# schaltplan.net
KiCad netlist of a schematic drawn in EAGLE
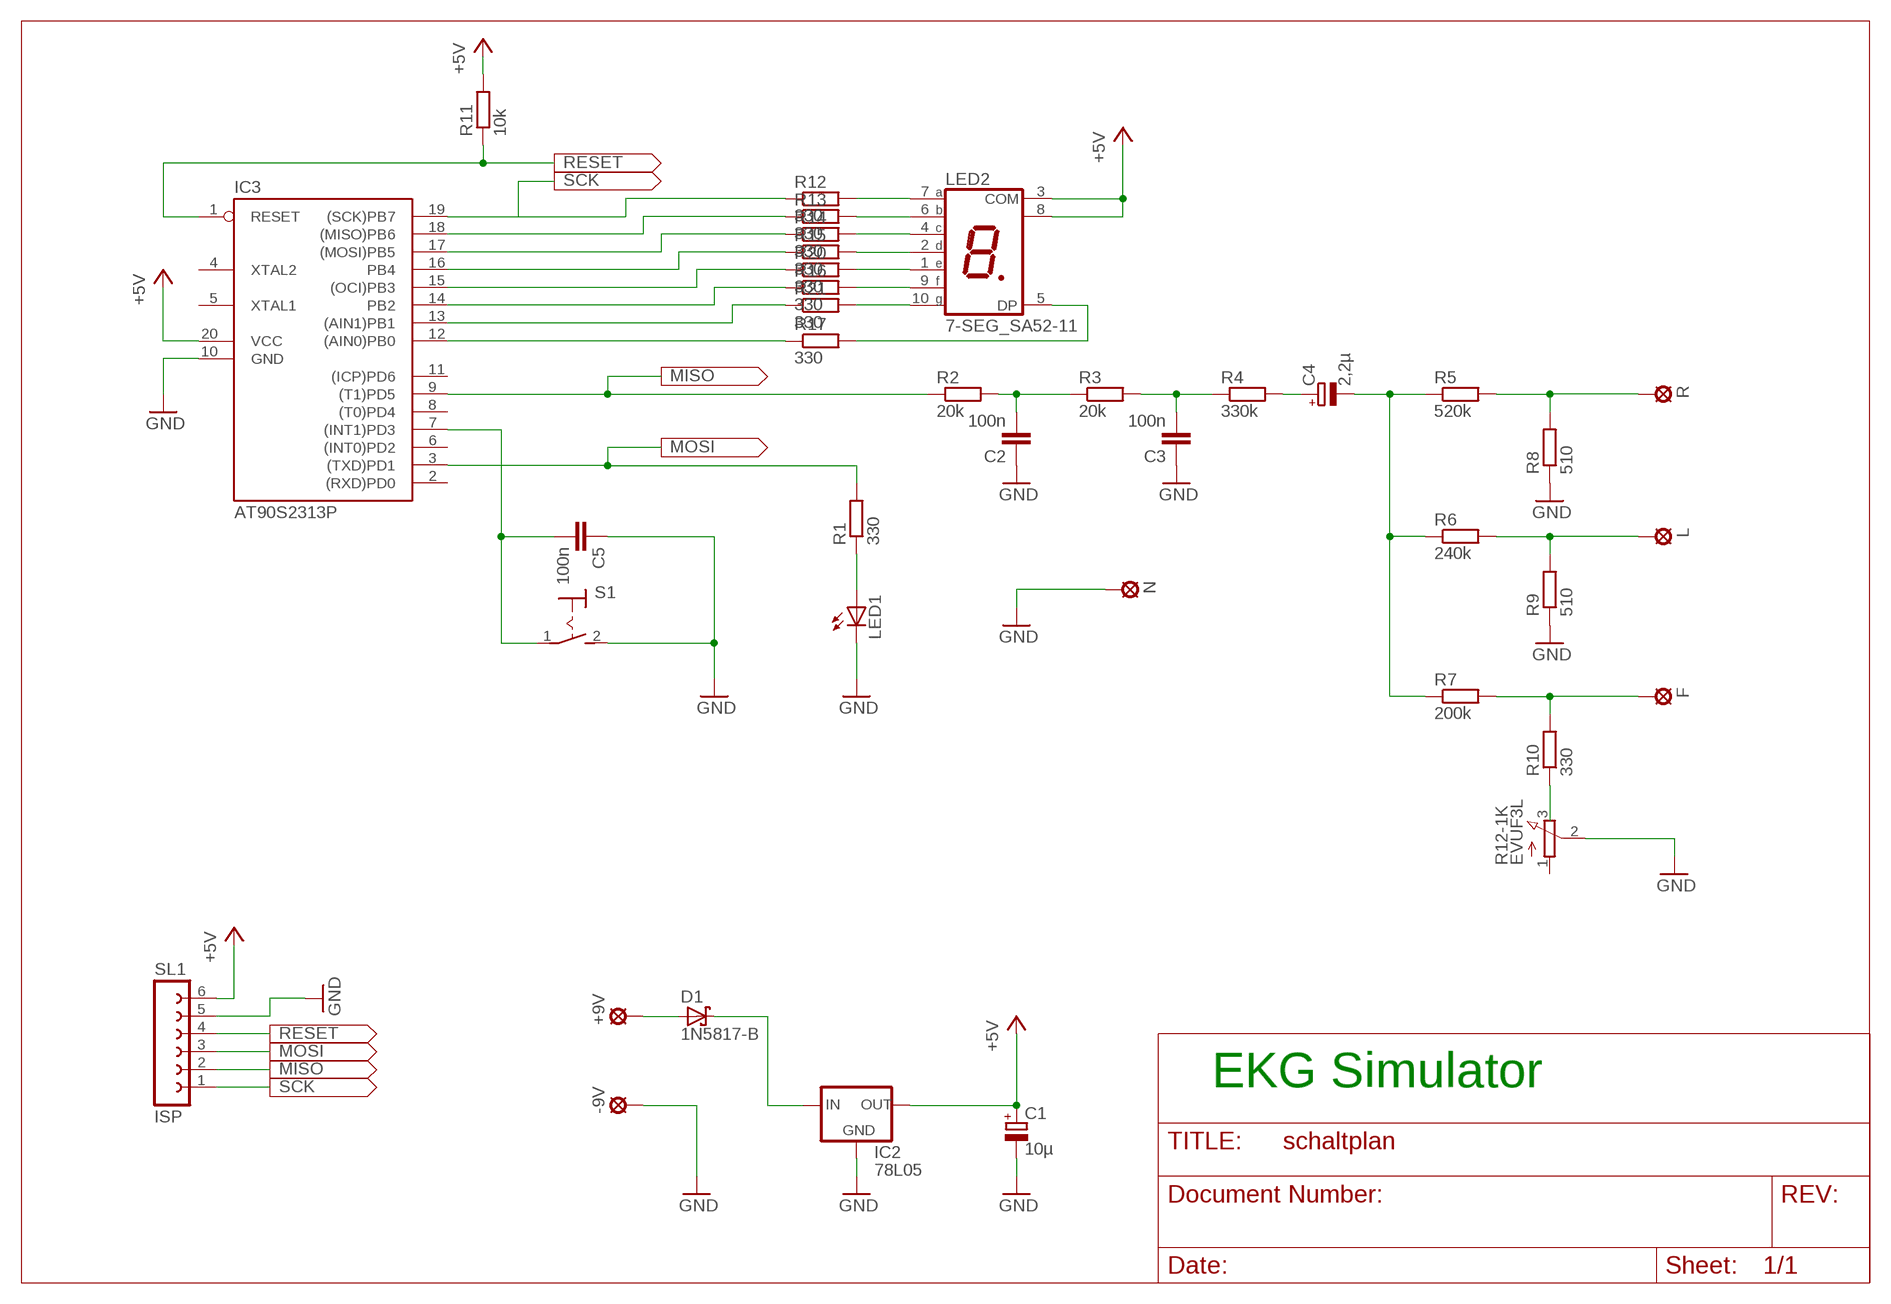
[diagram p0: schematic, sheet 1]

(export (version "E")
  (design (tool "Eeschema 10.0.6"))
  (components
    (comp (ref "+9V")
      (value "LSP10")
      (footprint "eagle-import:LSP10")
      (libsource (lib "eagle-import") (part "LSP10"))
    )
    (comp (ref "-9V")
      (value "LSP10")
      (footprint "eagle-import:LSP10")
      (libsource (lib "eagle-import") (part "LSP10"))
    )
    (comp (ref "C1")
      (value "10µ")
      (footprint "eagle-import:E2,5-6")
      (libsource (lib "eagle-import") (part "CPOL-EUE2.5-6"))
    )
    (comp (ref "C2")
      (value "100n")
      (footprint "eagle-import:C050-025X075")
      (libsource (lib "eagle-import") (part "C-EU050-025X075"))
    )
    (comp (ref "C3")
      (value "100n")
      (footprint "eagle-import:C050-025X075")
      (libsource (lib "eagle-import") (part "C-EU050-025X075"))
    )
    (comp (ref "C4")
      (value "2,2µ")
      (footprint "eagle-import:E2,5-5")
      (libsource (lib "eagle-import") (part "CPOL-EUE2.5-5"))
    )
    (comp (ref "C5")
      (value "100n")
      (footprint "eagle-import:C050-025X075")
      (libsource (lib "eagle-import") (part "C-EU050-025X075"))
    )
    (comp (ref "D1")
      (value "1N5817-B")
      (footprint "eagle-import:DO41-7.6")
      (libsource (lib "eagle-import") (part "1N5817-B"))
    )
    (comp (ref "F")
      (value "LSP10")
      (footprint "eagle-import:LSP10")
      (libsource (lib "eagle-import") (part "LSP10"))
    )
    (comp (ref "IC2")
      (value "78L05")
      (footprint "eagle-import:78LXX")
      (libsource (lib "eagle-import") (part "78LXX"))
    )
    (comp (ref "IC3")
      (value "AT90S2313P")
      (footprint "eagle-import:DIL20")
      (libsource (lib "eagle-import") (part "AT90S2313P"))
    )
    (comp (ref "L")
      (value "LSP10")
      (footprint "eagle-import:LSP10")
      (libsource (lib "eagle-import") (part "LSP10"))
    )
    (comp (ref "LED1")
      (value "LED3MM")
      (footprint "eagle-import:LED3MM")
      (libsource (lib "eagle-import") (part "LED3MM"))
    )
    (comp (ref "LED2")
      (value "7-SEG_SA52-11")
      (footprint "eagle-import:SA52-11")
      (libsource (lib "eagle-import") (part "7-SEG_SA52-11"))
    )
    (comp (ref "N")
      (value "LSP10")
      (footprint "eagle-import:LSP10")
      (libsource (lib "eagle-import") (part "LSP10"))
    )
    (comp (ref "R")
      (value "LSP10")
      (footprint "eagle-import:LSP10")
      (libsource (lib "eagle-import") (part "LSP10"))
    )
    (comp (ref "R1")
      (value "330")
      (footprint "eagle-import:0207_10")
      (libsource (lib "eagle-import") (part "R-EU_0207/10"))
    )
    (comp (ref "R2")
      (value "20k")
      (footprint "eagle-import:0207_10")
      (libsource (lib "eagle-import") (part "R-EU_0207/10"))
    )
    (comp (ref "R3")
      (value "20k")
      (footprint "eagle-import:0207_10")
      (libsource (lib "eagle-import") (part "R-EU_0207/10"))
    )
    (comp (ref "R4")
      (value "330k")
      (footprint "eagle-import:MINI_MELF-0204W")
      (libsource (lib "eagle-import") (part "R-EU_MELF0204W"))
    )
    (comp (ref "R5")
      (value "520k")
      (footprint "eagle-import:0207_10")
      (libsource (lib "eagle-import") (part "R-EU_0207/10"))
    )
    (comp (ref "R6")
      (value "240k")
      (footprint "eagle-import:0207_10")
      (libsource (lib "eagle-import") (part "R-EU_0207/10"))
    )
    (comp (ref "R7")
      (value "200k")
      (footprint "eagle-import:0207_10")
      (libsource (lib "eagle-import") (part "R-EU_0207/10"))
    )
    (comp (ref "R8")
      (value "510")
      (footprint "eagle-import:0207_10")
      (libsource (lib "eagle-import") (part "R-EU_0207/10"))
    )
    (comp (ref "R9")
      (value "510")
      (footprint "eagle-import:0207_10")
      (libsource (lib "eagle-import") (part "R-EU_0207/10"))
    )
    (comp (ref "R10")
      (value "330")
      (footprint "eagle-import:0207_10")
      (libsource (lib "eagle-import") (part "R-EU_0207/10"))
    )
    (comp (ref "R11")
      (value "10k")
      (footprint "eagle-import:MINI_MELF-0204W")
      (libsource (lib "eagle-import") (part "R-EU_MELF0204W"))
    )
    (comp (ref "R12")
      (value "330")
      (footprint "eagle-import:0207_10")
      (libsource (lib "eagle-import") (part "R-EU_0207/10"))
    )
    (comp (ref "R12-1K")
      (value "EVUF3L")
      (footprint "eagle-import:EVUFXL")
      (libsource (lib "eagle-import") (part "EVULF3"))
    )
    (comp (ref "R13")
      (value "330")
      (footprint "eagle-import:0207_10")
      (libsource (lib "eagle-import") (part "R-EU_0207/10"))
    )
    (comp (ref "R14")
      (value "330")
      (footprint "eagle-import:0207_10")
      (libsource (lib "eagle-import") (part "R-EU_0207/10"))
    )
    (comp (ref "R15")
      (value "330")
      (footprint "eagle-import:0207_10")
      (libsource (lib "eagle-import") (part "R-EU_0207/10"))
    )
    (comp (ref "R16")
      (value "330")
      (footprint "eagle-import:0207_10")
      (libsource (lib "eagle-import") (part "R-EU_0207/10"))
    )
    (comp (ref "R17")
      (value "330")
      (footprint "eagle-import:0207_10")
      (libsource (lib "eagle-import") (part "R-EU_0207/10"))
    )
    (comp (ref "R20")
      (value "330")
      (footprint "eagle-import:0207_10")
      (libsource (lib "eagle-import") (part "R-EU_0207/10"))
    )
    (comp (ref "R21")
      (value "330")
      (footprint "eagle-import:0207_10")
      (libsource (lib "eagle-import") (part "R-EU_0207/10"))
    )
    (comp (ref "S1")
      (value "MS243")
      (footprint "eagle-import:MS243")
      (libsource (lib "eagle-import") (part "MS243"))
    )
    (comp (ref "SL1")
      (value "ISP")
      (footprint "eagle-import:FE06")
      (libsource (lib "eagle-import") (part "FE06-1"))
    )
  )
  (nets
    (net (code "1") (name "+5V") (class "Default")
      (node (ref "C1") (pin "+") (pinfunction "+_+") (pintype "passive"))
      (node (ref "IC2") (pin "OUT") (pinfunction "OUT_OUT") (pintype "passive"))
      (node (ref "IC3") (pin "20") (pinfunction "VCC_20") (pintype "power_in"))
      (node (ref "LED2") (pin "3") (pinfunction "COM_3") (pintype "passive"))
      (node (ref "LED2") (pin "8") (pinfunction "COM_8") (pintype "passive"))
      (node (ref "R11") (pin "2") (pinfunction "2_2") (pintype "passive"))
      (node (ref "SL1") (pin "6") (pinfunction "6_6") (pintype "passive"))
    )
    (net (code "2") (name "/MISO") (class "Default")
      (node (ref "IC3") (pin "9") (pinfunction "(T1)PD5_9") (pintype "bidirectional"))
      (node (ref "R2") (pin "1") (pinfunction "1_1") (pintype "passive"))
      (node (ref "SL1") (pin "2") (pinfunction "2_2") (pintype "passive"))
    )
    (net (code "3") (name "/MOSI") (class "Default")
      (node (ref "IC3") (pin "3") (pinfunction "(TXD)PD1_3") (pintype "bidirectional"))
      (node (ref "R1") (pin "2") (pinfunction "2_2") (pintype "passive"))
      (node (ref "SL1") (pin "3") (pinfunction "3_3") (pintype "passive"))
    )
    (net (code "4") (name "GND") (class "Default")
      (node (ref "-9V") (pin "MP") (pinfunction "MP_MP") (pintype "passive"))
      (node (ref "C1") (pin "-") (pinfunction "-_-") (pintype "passive"))
      (node (ref "C2") (pin "1") (pinfunction "1_1") (pintype "passive"))
      (node (ref "C3") (pin "1") (pinfunction "1_1") (pintype "passive"))
      (node (ref "C5") (pin "1") (pinfunction "1_1") (pintype "passive"))
      (node (ref "IC2") (pin "GND") (pinfunction "GND_GND") (pintype "input"))
      (node (ref "IC3") (pin "10") (pinfunction "GND_10") (pintype "power_in"))
      (node (ref "LED1") (pin "K") (pinfunction "C_K") (pintype "passive"))
      (node (ref "N") (pin "MP") (pinfunction "MP_MP") (pintype "passive"))
      (node (ref "R12-1K") (pin "2") (pinfunction "S_2") (pintype "passive"))
      (node (ref "R8") (pin "1") (pinfunction "1_1") (pintype "passive"))
      (node (ref "R9") (pin "1") (pinfunction "1_1") (pintype "passive"))
      (node (ref "S1") (pin "2") (pinfunction "S_2") (pintype "passive"))
      (node (ref "SL1") (pin "5") (pinfunction "5_5") (pintype "passive"))
    )
    (net (code "5") (name "Net-(+9V-PadMP)") (class "Default")
      (node (ref "+9V") (pin "MP") (pinfunction "MP_MP") (pintype "passive"))
      (node (ref "D1") (pin "A") (pinfunction "A_A") (pintype "passive"))
    )
    (net (code "6") (name "Net-(C2-Pad2)") (class "Default")
      (node (ref "C2") (pin "2") (pinfunction "2_2") (pintype "passive"))
      (node (ref "R2") (pin "2") (pinfunction "2_2") (pintype "passive"))
      (node (ref "R3") (pin "1") (pinfunction "1_1") (pintype "passive"))
    )
    (net (code "7") (name "Net-(C3-Pad2)") (class "Default")
      (node (ref "C3") (pin "2") (pinfunction "2_2") (pintype "passive"))
      (node (ref "R3") (pin "2") (pinfunction "2_2") (pintype "passive"))
      (node (ref "R4") (pin "1") (pinfunction "1_1") (pintype "passive"))
    )
    (net (code "8") (name "Net-(C4-Pad+)") (class "Default")
      (node (ref "C4") (pin "+") (pinfunction "+_+") (pintype "passive"))
      (node (ref "R4") (pin "2") (pinfunction "2_2") (pintype "passive"))
    )
    (net (code "9") (name "Net-(C4-Pad-)") (class "Default")
      (node (ref "C4") (pin "-") (pinfunction "-_-") (pintype "passive"))
      (node (ref "R5") (pin "1") (pinfunction "1_1") (pintype "passive"))
      (node (ref "R6") (pin "1") (pinfunction "1_1") (pintype "passive"))
      (node (ref "R7") (pin "1") (pinfunction "1_1") (pintype "passive"))
    )
    (net (code "10") (name "Net-(D1-PadC)") (class "Default")
      (node (ref "D1") (pin "C") (pinfunction "C_C") (pintype "passive"))
      (node (ref "IC2") (pin "IN") (pinfunction "IN_IN") (pintype "input"))
    )
    (net (code "11") (name "Net-(F-PadMP)") (class "Default")
      (node (ref "F") (pin "MP") (pinfunction "MP_MP") (pintype "passive"))
      (node (ref "R10") (pin "2") (pinfunction "2_2") (pintype "passive"))
      (node (ref "R7") (pin "2") (pinfunction "2_2") (pintype "passive"))
    )
    (net (code "12") (name "Net-(IC3-(AIN0)PB0)") (class "Default")
      (node (ref "IC3") (pin "12") (pinfunction "(AIN0)PB0_12") (pintype "bidirectional"))
      (node (ref "R17") (pin "1") (pinfunction "1_1") (pintype "passive"))
    )
    (net (code "13") (name "Net-(IC3-(AIN1)PB1)") (class "Default")
      (node (ref "IC3") (pin "13") (pinfunction "(AIN1)PB1_13") (pintype "bidirectional"))
      (node (ref "R21") (pin "1") (pinfunction "1_1") (pintype "passive"))
    )
    (net (code "14") (name "Net-(IC3-(INT1)PD3)") (class "Default")
      (node (ref "C5") (pin "2") (pinfunction "2_2") (pintype "passive"))
      (node (ref "IC3") (pin "7") (pinfunction "(INT1)PD3_7") (pintype "bidirectional"))
      (node (ref "S1") (pin "1") (pinfunction "P_1") (pintype "passive"))
    )
    (net (code "15") (name "Net-(IC3-(MISO)PB6)") (class "Default")
      (node (ref "IC3") (pin "18") (pinfunction "(MISO)PB6_18") (pintype "bidirectional"))
      (node (ref "R13") (pin "1") (pinfunction "1_1") (pintype "passive"))
    )
    (net (code "16") (name "Net-(IC3-(MOSI)PB5)") (class "Default")
      (node (ref "IC3") (pin "17") (pinfunction "(MOSI)PB5_17") (pintype "bidirectional"))
      (node (ref "R14") (pin "1") (pinfunction "1_1") (pintype "passive"))
    )
    (net (code "17") (name "Net-(IC3-(OCI)PB3)") (class "Default")
      (node (ref "IC3") (pin "15") (pinfunction "(OCI)PB3_15") (pintype "bidirectional"))
      (node (ref "R20") (pin "1") (pinfunction "1_1") (pintype "passive"))
    )
    (net (code "18") (name "Net-(IC3-(SCK)PB7)") (class "Default")
      (node (ref "IC3") (pin "19") (pinfunction "(SCK)PB7_19") (pintype "bidirectional"))
      (node (ref "R12") (pin "1") (pinfunction "1_1") (pintype "passive"))
    )
    (net (code "19") (name "Net-(IC3-PB2)") (class "Default")
      (node (ref "IC3") (pin "14") (pinfunction "PB2_14") (pintype "bidirectional"))
      (node (ref "R16") (pin "1") (pinfunction "1_1") (pintype "passive"))
    )
    (net (code "20") (name "Net-(IC3-PB4)") (class "Default")
      (node (ref "IC3") (pin "16") (pinfunction "PB4_16") (pintype "bidirectional"))
      (node (ref "R15") (pin "1") (pinfunction "1_1") (pintype "passive"))
    )
    (net (code "21") (name "Net-(IC3-RESET)") (class "Default")
      (node (ref "IC3") (pin "1") (pinfunction "RESET_1") (pintype "bidirectional"))
      (node (ref "R11") (pin "1") (pinfunction "1_1") (pintype "passive"))
    )
    (net (code "22") (name "Net-(L-PadMP)") (class "Default")
      (node (ref "L") (pin "MP") (pinfunction "MP_MP") (pintype "passive"))
      (node (ref "R6") (pin "2") (pinfunction "2_2") (pintype "passive"))
      (node (ref "R9") (pin "2") (pinfunction "2_2") (pintype "passive"))
    )
    (net (code "23") (name "Net-(LED1-PadA)") (class "Default")
      (node (ref "LED1") (pin "A") (pinfunction "A_A") (pintype "passive"))
      (node (ref "R1") (pin "1") (pinfunction "1_1") (pintype "passive"))
    )
    (net (code "24") (name "Net-(LED2-A)") (class "Default")
      (node (ref "LED2") (pin "7") (pinfunction "A_7") (pintype "passive"))
      (node (ref "R12") (pin "2") (pinfunction "2_2") (pintype "passive"))
    )
    (net (code "25") (name "Net-(LED2-B)") (class "Default")
      (node (ref "LED2") (pin "6") (pinfunction "B_6") (pintype "passive"))
      (node (ref "R13") (pin "2") (pinfunction "2_2") (pintype "passive"))
    )
    (net (code "26") (name "Net-(LED2-C)") (class "Default")
      (node (ref "LED2") (pin "4") (pinfunction "C_4") (pintype "passive"))
      (node (ref "R14") (pin "2") (pinfunction "2_2") (pintype "passive"))
    )
    (net (code "27") (name "Net-(LED2-D)") (class "Default")
      (node (ref "LED2") (pin "2") (pinfunction "D_2") (pintype "passive"))
      (node (ref "R15") (pin "2") (pinfunction "2_2") (pintype "passive"))
    )
    (net (code "28") (name "Net-(LED2-DP)") (class "Default")
      (node (ref "LED2") (pin "5") (pinfunction "DP_5") (pintype "passive"))
      (node (ref "R17") (pin "2") (pinfunction "2_2") (pintype "passive"))
    )
    (net (code "29") (name "Net-(LED2-E)") (class "Default")
      (node (ref "LED2") (pin "1") (pinfunction "E_1") (pintype "passive"))
      (node (ref "R20") (pin "2") (pinfunction "2_2") (pintype "passive"))
    )
    (net (code "30") (name "Net-(LED2-F)") (class "Default")
      (node (ref "LED2") (pin "9") (pinfunction "F_9") (pintype "passive"))
      (node (ref "R16") (pin "2") (pinfunction "2_2") (pintype "passive"))
    )
    (net (code "31") (name "Net-(LED2-G)") (class "Default")
      (node (ref "LED2") (pin "10") (pinfunction "G_10") (pintype "passive"))
      (node (ref "R21") (pin "2") (pinfunction "2_2") (pintype "passive"))
    )
    (net (code "32") (name "Net-(R-PadMP)") (class "Default")
      (node (ref "R") (pin "MP") (pinfunction "MP_MP") (pintype "passive"))
      (node (ref "R5") (pin "2") (pinfunction "2_2") (pintype "passive"))
      (node (ref "R8") (pin "2") (pinfunction "2_2") (pintype "passive"))
    )
    (net (code "33") (name "unconnected-(IC3-(ICP)PD6-Pad11)") (class "Default")
      (node (ref "IC3") (pin "11") (pinfunction "(ICP)PD6_11") (pintype "bidirectional"))
    )
    (net (code "34") (name "unconnected-(IC3-(INT0)PD2-Pad6)") (class "Default")
      (node (ref "IC3") (pin "6") (pinfunction "(INT0)PD2_6") (pintype "bidirectional"))
    )
    (net (code "35") (name "unconnected-(IC3-(RXD)PD0-Pad2)") (class "Default")
      (node (ref "IC3") (pin "2") (pinfunction "(RXD)PD0_2") (pintype "bidirectional"))
    )
    (net (code "36") (name "unconnected-(IC3-(T0)PD4-Pad8)") (class "Default")
      (node (ref "IC3") (pin "8") (pinfunction "(T0)PD4_8") (pintype "bidirectional"))
    )
    (net (code "37") (name "unconnected-(IC3-XTAL1-Pad5)") (class "Default")
      (node (ref "IC3") (pin "5") (pinfunction "XTAL1_5") (pintype "bidirectional"))
    )
    (net (code "38") (name "unconnected-(IC3-XTAL2-Pad4)") (class "Default")
      (node (ref "IC3") (pin "4") (pinfunction "XTAL2_4") (pintype "bidirectional"))
    )
    (net (code "39") (name "unconnected-(R10-Pad1)") (class "Default")
      (node (ref "R10") (pin "1") (pinfunction "1_1") (pintype "passive"))
    )
    (net (code "40") (name "unconnected-(R12-1K-A-Pad1)") (class "Default")
      (node (ref "R12-1K") (pin "1") (pinfunction "A_1") (pintype "passive"))
    )
    (net (code "41") (name "unconnected-(R12-1K-E-Pad3)") (class "Default")
      (node (ref "R12-1K") (pin "3") (pinfunction "E_3") (pintype "passive"))
    )
    (net (code "42") (name "unconnected-(SL1-Pad1)") (class "Default")
      (node (ref "SL1") (pin "1") (pinfunction "1_1") (pintype "passive"))
    )
    (net (code "43") (name "unconnected-(SL1-Pad4)") (class "Default")
      (node (ref "SL1") (pin "4") (pinfunction "4_4") (pintype "passive"))
    )
  )
)
